# Control.net
KiCad netlist of a schematic drawn in Altium Designer
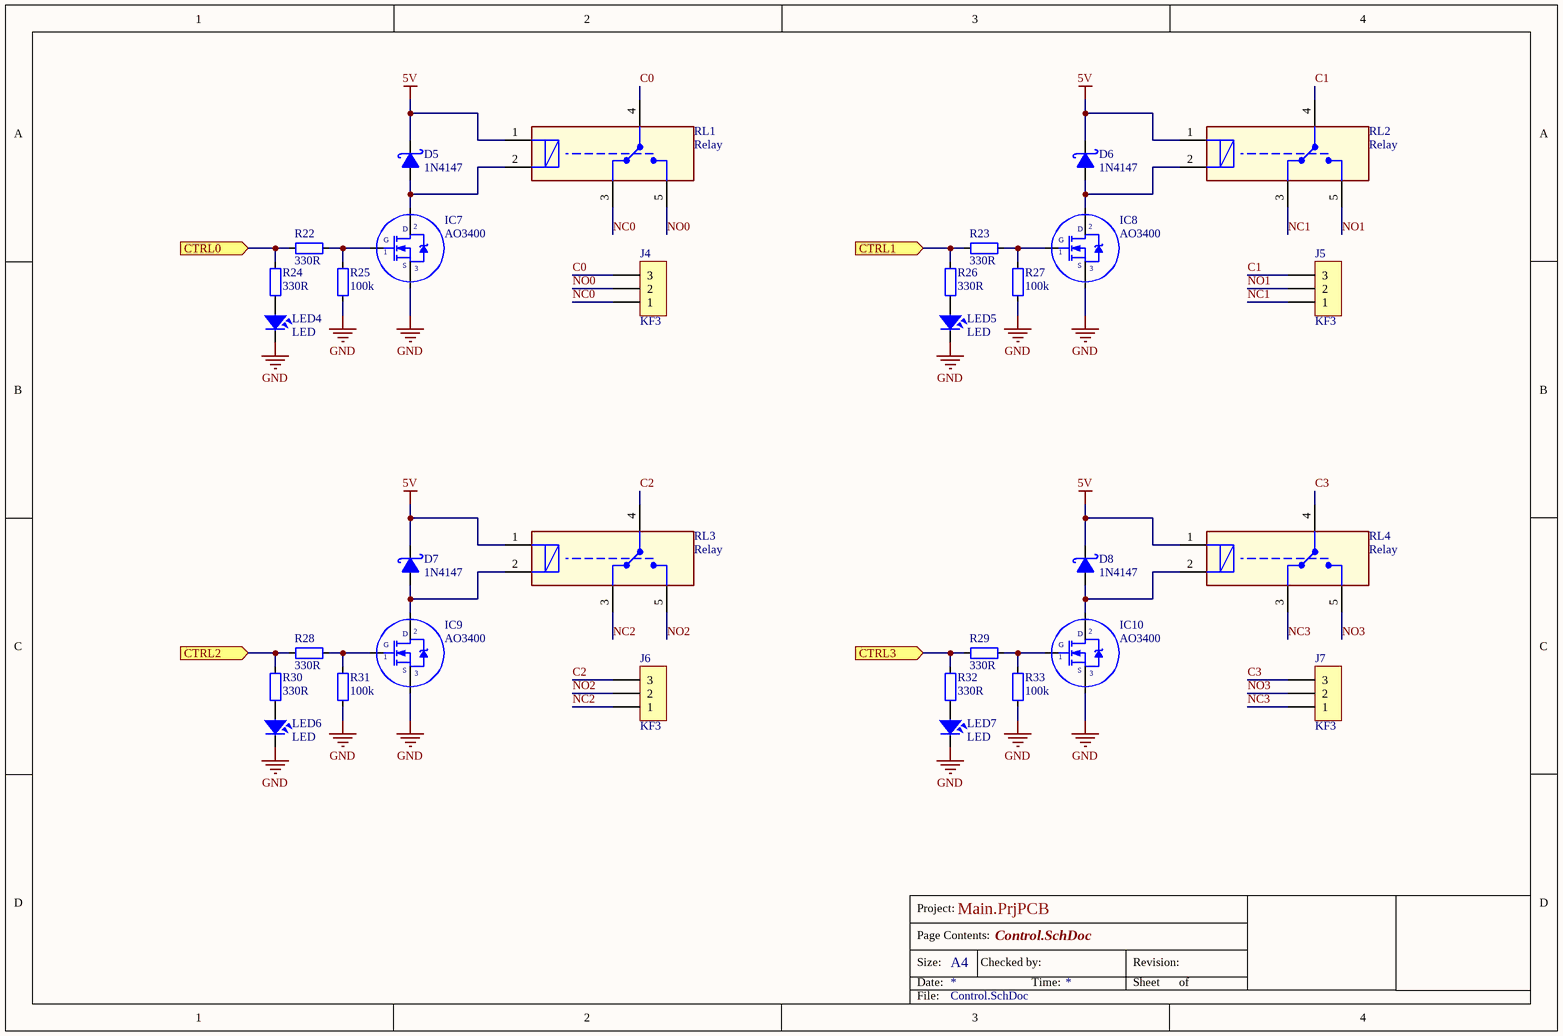
[diagram p0: Control.SchDoc]

(export (version "E")
  (design (tool "Eeschema 10.0.6"))
  (components
    (comp (ref "D5")
      (value "1N4147")
      (footprint "DIO_R_SMD")
      (description "Generic Diode Schottky")
      (libsource (lib "My Library") (part "Diode Schottky"))
    )
    (comp (ref "D6")
      (value "1N4147")
      (footprint "DIO_R_SMD")
      (description "Generic Diode Schottky")
      (libsource (lib "My Library") (part "Diode Schottky"))
    )
    (comp (ref "D7")
      (value "1N4147")
      (footprint "DIO_R_SMD")
      (description "Generic Diode Schottky")
      (libsource (lib "My Library") (part "Diode Schottky"))
    )
    (comp (ref "D8")
      (value "1N4147")
      (footprint "DIO_R_SMD")
      (description "Generic Diode Schottky")
      (libsource (lib "My Library") (part "Diode Schottky"))
    )
    (comp (ref "IC7")
      (value "AO3400")
      (footprint "SOT23A")
      (description "Generic N Channel MOSFET")
      (libsource (lib "My Library") (part "MOSFET_N"))
    )
    (comp (ref "IC8")
      (value "AO3400")
      (footprint "SOT23A")
      (description "Generic N Channel MOSFET")
      (libsource (lib "My Library") (part "MOSFET_N"))
    )
    (comp (ref "IC9")
      (value "AO3400")
      (footprint "SOT23A")
      (description "Generic N Channel MOSFET")
      (libsource (lib "My Library") (part "MOSFET_N"))
    )
    (comp (ref "IC10")
      (value "AO3400")
      (footprint "SOT23A")
      (description "Generic N Channel MOSFET")
      (libsource (lib "My Library") (part "MOSFET_N"))
    )
    (comp (ref "J4")
      (value "KF3")
      (footprint "KF3-3.5-EDG")
      (fields
        (field (name "MANUFACTURER") "Würth Elektronik eiSos GmbH")
        (field (name "PARTNO") "691103110003")
        (field (name "CREATED BY") "Karrer Zheng")
      )
      (libsource (lib "My Library") (part "KF3"))
    )
    (comp (ref "J5")
      (value "KF3")
      (footprint "KF3-3.5-EDG")
      (fields
        (field (name "MANUFACTURER") "Würth Elektronik eiSos GmbH")
        (field (name "PARTNO") "691103110003")
        (field (name "CREATED BY") "Karrer Zheng")
      )
      (libsource (lib "My Library") (part "KF3"))
    )
    (comp (ref "J6")
      (value "KF3")
      (footprint "KF3-3.5-EDG")
      (fields
        (field (name "MANUFACTURER") "Würth Elektronik eiSos GmbH")
        (field (name "PARTNO") "691103110003")
        (field (name "CREATED BY") "Karrer Zheng")
      )
      (libsource (lib "My Library") (part "KF3"))
    )
    (comp (ref "J7")
      (value "KF3")
      (footprint "KF3-3.5-EDG")
      (fields
        (field (name "MANUFACTURER") "Würth Elektronik eiSos GmbH")
        (field (name "PARTNO") "691103110003")
        (field (name "CREATED BY") "Karrer Zheng")
      )
      (libsource (lib "My Library") (part "KF3"))
    )
    (comp (ref "LED4")
      (value "LED")
      (footprint "LED-0805-Red")
      (description "LED Single colour Green and Red")
      (libsource (lib "My Library") (part "LED"))
    )
    (comp (ref "LED5")
      (value "LED")
      (footprint "LED-0805-Red")
      (description "LED Single colour Green and Red")
      (libsource (lib "My Library") (part "LED"))
    )
    (comp (ref "LED6")
      (value "LED")
      (footprint "LED-0805-Red")
      (description "LED Single colour Green and Red")
      (libsource (lib "My Library") (part "LED"))
    )
    (comp (ref "LED7")
      (value "LED")
      (footprint "LED-0805-Red")
      (description "LED Single colour Green and Red")
      (libsource (lib "My Library") (part "LED"))
    )
    (comp (ref "R22")
      (value "330R")
      (footprint "RES-SMD-0805")
      (description "Resistor")
      (fields
        (field (name "MANUFACTURER") "Generic Components")
        (field (name "PUBLISHER") "Altium Hobart Technology Centre")
      )
      (libsource (lib "My Library") (part "Resistor - SMD"))
    )
    (comp (ref "R23")
      (value "330R")
      (footprint "RES-SMD-0805")
      (description "Resistor")
      (fields
        (field (name "MANUFACTURER") "Generic Components")
        (field (name "PUBLISHER") "Altium Hobart Technology Centre")
      )
      (libsource (lib "My Library") (part "Resistor - SMD"))
    )
    (comp (ref "R24")
      (value "330R")
      (footprint "RES-SMD-0805")
      (description "Resistor")
      (fields
        (field (name "MANUFACTURER") "Generic Components")
        (field (name "PUBLISHER") "Altium Hobart Technology Centre")
      )
      (libsource (lib "My Library") (part "Resistor - SMD"))
    )
    (comp (ref "R25")
      (value "100k")
      (footprint "RES-SMD-0805")
      (description "Resistor")
      (fields
        (field (name "MANUFACTURER") "Generic Components")
        (field (name "PUBLISHER") "Altium Hobart Technology Centre")
      )
      (libsource (lib "My Library") (part "Resistor - SMD"))
    )
    (comp (ref "R26")
      (value "330R")
      (footprint "RES-SMD-0805")
      (description "Resistor")
      (fields
        (field (name "MANUFACTURER") "Generic Components")
        (field (name "PUBLISHER") "Altium Hobart Technology Centre")
      )
      (libsource (lib "My Library") (part "Resistor - SMD"))
    )
    (comp (ref "R27")
      (value "100k")
      (footprint "RES-SMD-0805")
      (description "Resistor")
      (fields
        (field (name "MANUFACTURER") "Generic Components")
        (field (name "PUBLISHER") "Altium Hobart Technology Centre")
      )
      (libsource (lib "My Library") (part "Resistor - SMD"))
    )
    (comp (ref "R28")
      (value "330R")
      (footprint "RES-SMD-0805")
      (description "Resistor")
      (fields
        (field (name "MANUFACTURER") "Generic Components")
        (field (name "PUBLISHER") "Altium Hobart Technology Centre")
      )
      (libsource (lib "My Library") (part "Resistor - SMD"))
    )
    (comp (ref "R29")
      (value "330R")
      (footprint "RES-SMD-0805")
      (description "Resistor")
      (fields
        (field (name "MANUFACTURER") "Generic Components")
        (field (name "PUBLISHER") "Altium Hobart Technology Centre")
      )
      (libsource (lib "My Library") (part "Resistor - SMD"))
    )
    (comp (ref "R30")
      (value "330R")
      (footprint "RES-SMD-0805")
      (description "Resistor")
      (fields
        (field (name "MANUFACTURER") "Generic Components")
        (field (name "PUBLISHER") "Altium Hobart Technology Centre")
      )
      (libsource (lib "My Library") (part "Resistor - SMD"))
    )
    (comp (ref "R31")
      (value "100k")
      (footprint "RES-SMD-0805")
      (description "Resistor")
      (fields
        (field (name "MANUFACTURER") "Generic Components")
        (field (name "PUBLISHER") "Altium Hobart Technology Centre")
      )
      (libsource (lib "My Library") (part "Resistor - SMD"))
    )
    (comp (ref "R32")
      (value "330R")
      (footprint "RES-SMD-0805")
      (description "Resistor")
      (fields
        (field (name "MANUFACTURER") "Generic Components")
        (field (name "PUBLISHER") "Altium Hobart Technology Centre")
      )
      (libsource (lib "My Library") (part "Resistor - SMD"))
    )
    (comp (ref "R33")
      (value "100k")
      (footprint "RES-SMD-0805")
      (description "Resistor")
      (fields
        (field (name "MANUFACTURER") "Generic Components")
        (field (name "PUBLISHER") "Altium Hobart Technology Centre")
      )
      (libsource (lib "My Library") (part "Resistor - SMD"))
    )
    (comp (ref "RL1")
      (value "Relay")
      (footprint "HF115F-XXX-1Z")
      (description "Relay 12V, 220VAC/5A, 4 pins")
      (libsource (lib "My Library") (part "Relay_HF"))
    )
    (comp (ref "RL2")
      (value "Relay")
      (footprint "HF115F-XXX-1Z")
      (description "Relay 12V, 220VAC/5A, 4 pins")
      (libsource (lib "My Library") (part "Relay_HF"))
    )
    (comp (ref "RL3")
      (value "Relay")
      (footprint "HF115F-XXX-1Z")
      (description "Relay 12V, 220VAC/5A, 4 pins")
      (libsource (lib "My Library") (part "Relay_HF"))
    )
    (comp (ref "RL4")
      (value "Relay")
      (footprint "HF115F-XXX-1Z")
      (description "Relay 12V, 220VAC/5A, 4 pins")
      (libsource (lib "My Library") (part "Relay_HF"))
    )
  )
  (nets
    (net (code "1") (name "/C0") (class "Default")
      (node (ref "J4") (pin "3") (pinfunction "3_3") (pintype "passive"))
      (node (ref "RL1") (pin "4") (pinfunction "C_4") (pintype "power_in"))
    )
    (net (code "2") (name "/C1") (class "Default")
      (node (ref "J5") (pin "3") (pinfunction "3_3") (pintype "passive"))
      (node (ref "RL2") (pin "4") (pinfunction "C_4") (pintype "power_in"))
    )
    (net (code "3") (name "/C2") (class "Default")
      (node (ref "J6") (pin "3") (pinfunction "3_3") (pintype "passive"))
      (node (ref "RL3") (pin "4") (pinfunction "C_4") (pintype "power_in"))
    )
    (net (code "4") (name "/C3") (class "Default")
      (node (ref "J7") (pin "3") (pinfunction "3_3") (pintype "passive"))
      (node (ref "RL4") (pin "4") (pinfunction "C_4") (pintype "power_in"))
    )
    (net (code "5") (name "/CTRL0") (class "Default")
      (node (ref "R22") (pin "1") (pinfunction "1_1") (pintype "passive"))
      (node (ref "R24") (pin "1") (pinfunction "1_1") (pintype "passive"))
    )
    (net (code "6") (name "/CTRL1") (class "Default")
      (node (ref "R23") (pin "1") (pinfunction "1_1") (pintype "passive"))
      (node (ref "R26") (pin "1") (pinfunction "1_1") (pintype "passive"))
    )
    (net (code "7") (name "/CTRL2") (class "Default")
      (node (ref "R28") (pin "1") (pinfunction "1_1") (pintype "passive"))
      (node (ref "R30") (pin "1") (pinfunction "1_1") (pintype "passive"))
    )
    (net (code "8") (name "/CTRL3") (class "Default")
      (node (ref "R29") (pin "1") (pinfunction "1_1") (pintype "passive"))
      (node (ref "R32") (pin "1") (pinfunction "1_1") (pintype "passive"))
    )
    (net (code "9") (name "/NC0") (class "Default")
      (node (ref "J4") (pin "1") (pinfunction "1_1") (pintype "passive"))
      (node (ref "RL1") (pin "3") (pinfunction "NC_3") (pintype "power_in"))
    )
    (net (code "10") (name "/NC1") (class "Default")
      (node (ref "J5") (pin "1") (pinfunction "1_1") (pintype "passive"))
      (node (ref "RL2") (pin "3") (pinfunction "NC_3") (pintype "power_in"))
    )
    (net (code "11") (name "/NC2") (class "Default")
      (node (ref "J6") (pin "1") (pinfunction "1_1") (pintype "passive"))
      (node (ref "RL3") (pin "3") (pinfunction "NC_3") (pintype "power_in"))
    )
    (net (code "12") (name "/NC3") (class "Default")
      (node (ref "J7") (pin "1") (pinfunction "1_1") (pintype "passive"))
      (node (ref "RL4") (pin "3") (pinfunction "NC_3") (pintype "power_in"))
    )
    (net (code "13") (name "/NO0") (class "Default")
      (node (ref "J4") (pin "2") (pinfunction "2_2") (pintype "passive"))
      (node (ref "RL1") (pin "5") (pinfunction "NO_5") (pintype "power_in"))
    )
    (net (code "14") (name "/NO1") (class "Default")
      (node (ref "J5") (pin "2") (pinfunction "2_2") (pintype "passive"))
      (node (ref "RL2") (pin "5") (pinfunction "NO_5") (pintype "power_in"))
    )
    (net (code "15") (name "/NO2") (class "Default")
      (node (ref "J6") (pin "2") (pinfunction "2_2") (pintype "passive"))
      (node (ref "RL3") (pin "5") (pinfunction "NO_5") (pintype "power_in"))
    )
    (net (code "16") (name "/NO3") (class "Default")
      (node (ref "J7") (pin "2") (pinfunction "2_2") (pintype "passive"))
      (node (ref "RL4") (pin "5") (pinfunction "NO_5") (pintype "power_in"))
    )
    (net (code "17") (name "5V") (class "Default")
      (node (ref "D5") (pin "2") (pinfunction "K_2") (pintype "passive"))
      (node (ref "D6") (pin "2") (pinfunction "K_2") (pintype "passive"))
      (node (ref "D7") (pin "2") (pinfunction "K_2") (pintype "passive"))
      (node (ref "D8") (pin "2") (pinfunction "K_2") (pintype "passive"))
      (node (ref "RL1") (pin "1") (pinfunction "+_1") (pintype "power_in"))
      (node (ref "RL2") (pin "1") (pinfunction "+_1") (pintype "power_in"))
      (node (ref "RL3") (pin "1") (pinfunction "+_1") (pintype "power_in"))
      (node (ref "RL4") (pin "1") (pinfunction "+_1") (pintype "power_in"))
    )
    (net (code "18") (name "GND") (class "Default")
      (node (ref "IC10") (pin "3") (pinfunction "S_3") (pintype "passive"))
      (node (ref "IC7") (pin "3") (pinfunction "S_3") (pintype "passive"))
      (node (ref "IC8") (pin "3") (pinfunction "S_3") (pintype "passive"))
      (node (ref "IC9") (pin "3") (pinfunction "S_3") (pintype "passive"))
      (node (ref "LED4") (pin "2") (pinfunction "2_2") (pintype "passive"))
      (node (ref "LED5") (pin "2") (pinfunction "2_2") (pintype "passive"))
      (node (ref "LED6") (pin "2") (pinfunction "2_2") (pintype "passive"))
      (node (ref "LED7") (pin "2") (pinfunction "2_2") (pintype "passive"))
      (node (ref "R25") (pin "1") (pinfunction "1_1") (pintype "passive"))
      (node (ref "R27") (pin "1") (pinfunction "1_1") (pintype "passive"))
      (node (ref "R31") (pin "1") (pinfunction "1_1") (pintype "passive"))
      (node (ref "R33") (pin "1") (pinfunction "1_1") (pintype "passive"))
    )
    (net (code "19") (name "Net-(D5-A)") (class "Default")
      (node (ref "D5") (pin "1") (pinfunction "A_1") (pintype "passive"))
      (node (ref "IC7") (pin "2") (pinfunction "D_2") (pintype "passive"))
      (node (ref "RL1") (pin "2") (pinfunction "-_2") (pintype "passive"))
    )
    (net (code "20") (name "Net-(D6-A)") (class "Default")
      (node (ref "D6") (pin "1") (pinfunction "A_1") (pintype "passive"))
      (node (ref "IC8") (pin "2") (pinfunction "D_2") (pintype "passive"))
      (node (ref "RL2") (pin "2") (pinfunction "-_2") (pintype "passive"))
    )
    (net (code "21") (name "Net-(D7-A)") (class "Default")
      (node (ref "D7") (pin "1") (pinfunction "A_1") (pintype "passive"))
      (node (ref "IC9") (pin "2") (pinfunction "D_2") (pintype "passive"))
      (node (ref "RL3") (pin "2") (pinfunction "-_2") (pintype "passive"))
    )
    (net (code "22") (name "Net-(D8-A)") (class "Default")
      (node (ref "D8") (pin "1") (pinfunction "A_1") (pintype "passive"))
      (node (ref "IC10") (pin "2") (pinfunction "D_2") (pintype "passive"))
      (node (ref "RL4") (pin "2") (pinfunction "-_2") (pintype "passive"))
    )
    (net (code "23") (name "Net-(IC7-G)") (class "Default")
      (node (ref "IC7") (pin "1") (pinfunction "G_1") (pintype "passive"))
      (node (ref "R22") (pin "2") (pinfunction "2_2") (pintype "passive"))
      (node (ref "R25") (pin "2") (pinfunction "2_2") (pintype "passive"))
    )
    (net (code "24") (name "Net-(IC8-G)") (class "Default")
      (node (ref "IC8") (pin "1") (pinfunction "G_1") (pintype "passive"))
      (node (ref "R23") (pin "2") (pinfunction "2_2") (pintype "passive"))
      (node (ref "R27") (pin "2") (pinfunction "2_2") (pintype "passive"))
    )
    (net (code "25") (name "Net-(IC9-G)") (class "Default")
      (node (ref "IC9") (pin "1") (pinfunction "G_1") (pintype "passive"))
      (node (ref "R28") (pin "2") (pinfunction "2_2") (pintype "passive"))
      (node (ref "R31") (pin "2") (pinfunction "2_2") (pintype "passive"))
    )
    (net (code "26") (name "Net-(IC10-G)") (class "Default")
      (node (ref "IC10") (pin "1") (pinfunction "G_1") (pintype "passive"))
      (node (ref "R29") (pin "2") (pinfunction "2_2") (pintype "passive"))
      (node (ref "R33") (pin "2") (pinfunction "2_2") (pintype "passive"))
    )
    (net (code "27") (name "Net-(LED4-Pad1)") (class "Default")
      (node (ref "LED4") (pin "1") (pinfunction "1_1") (pintype "passive"))
      (node (ref "R24") (pin "2") (pinfunction "2_2") (pintype "passive"))
    )
    (net (code "28") (name "Net-(LED5-Pad1)") (class "Default")
      (node (ref "LED5") (pin "1") (pinfunction "1_1") (pintype "passive"))
      (node (ref "R26") (pin "2") (pinfunction "2_2") (pintype "passive"))
    )
    (net (code "29") (name "Net-(LED6-Pad1)") (class "Default")
      (node (ref "LED6") (pin "1") (pinfunction "1_1") (pintype "passive"))
      (node (ref "R30") (pin "2") (pinfunction "2_2") (pintype "passive"))
    )
    (net (code "30") (name "Net-(LED7-Pad1)") (class "Default")
      (node (ref "LED7") (pin "1") (pinfunction "1_1") (pintype "passive"))
      (node (ref "R32") (pin "2") (pinfunction "2_2") (pintype "passive"))
    )
  )
)
